# 1-Schematic_dra-30-vox.net
KiCad netlist of a schematic drawn in EasyEDA
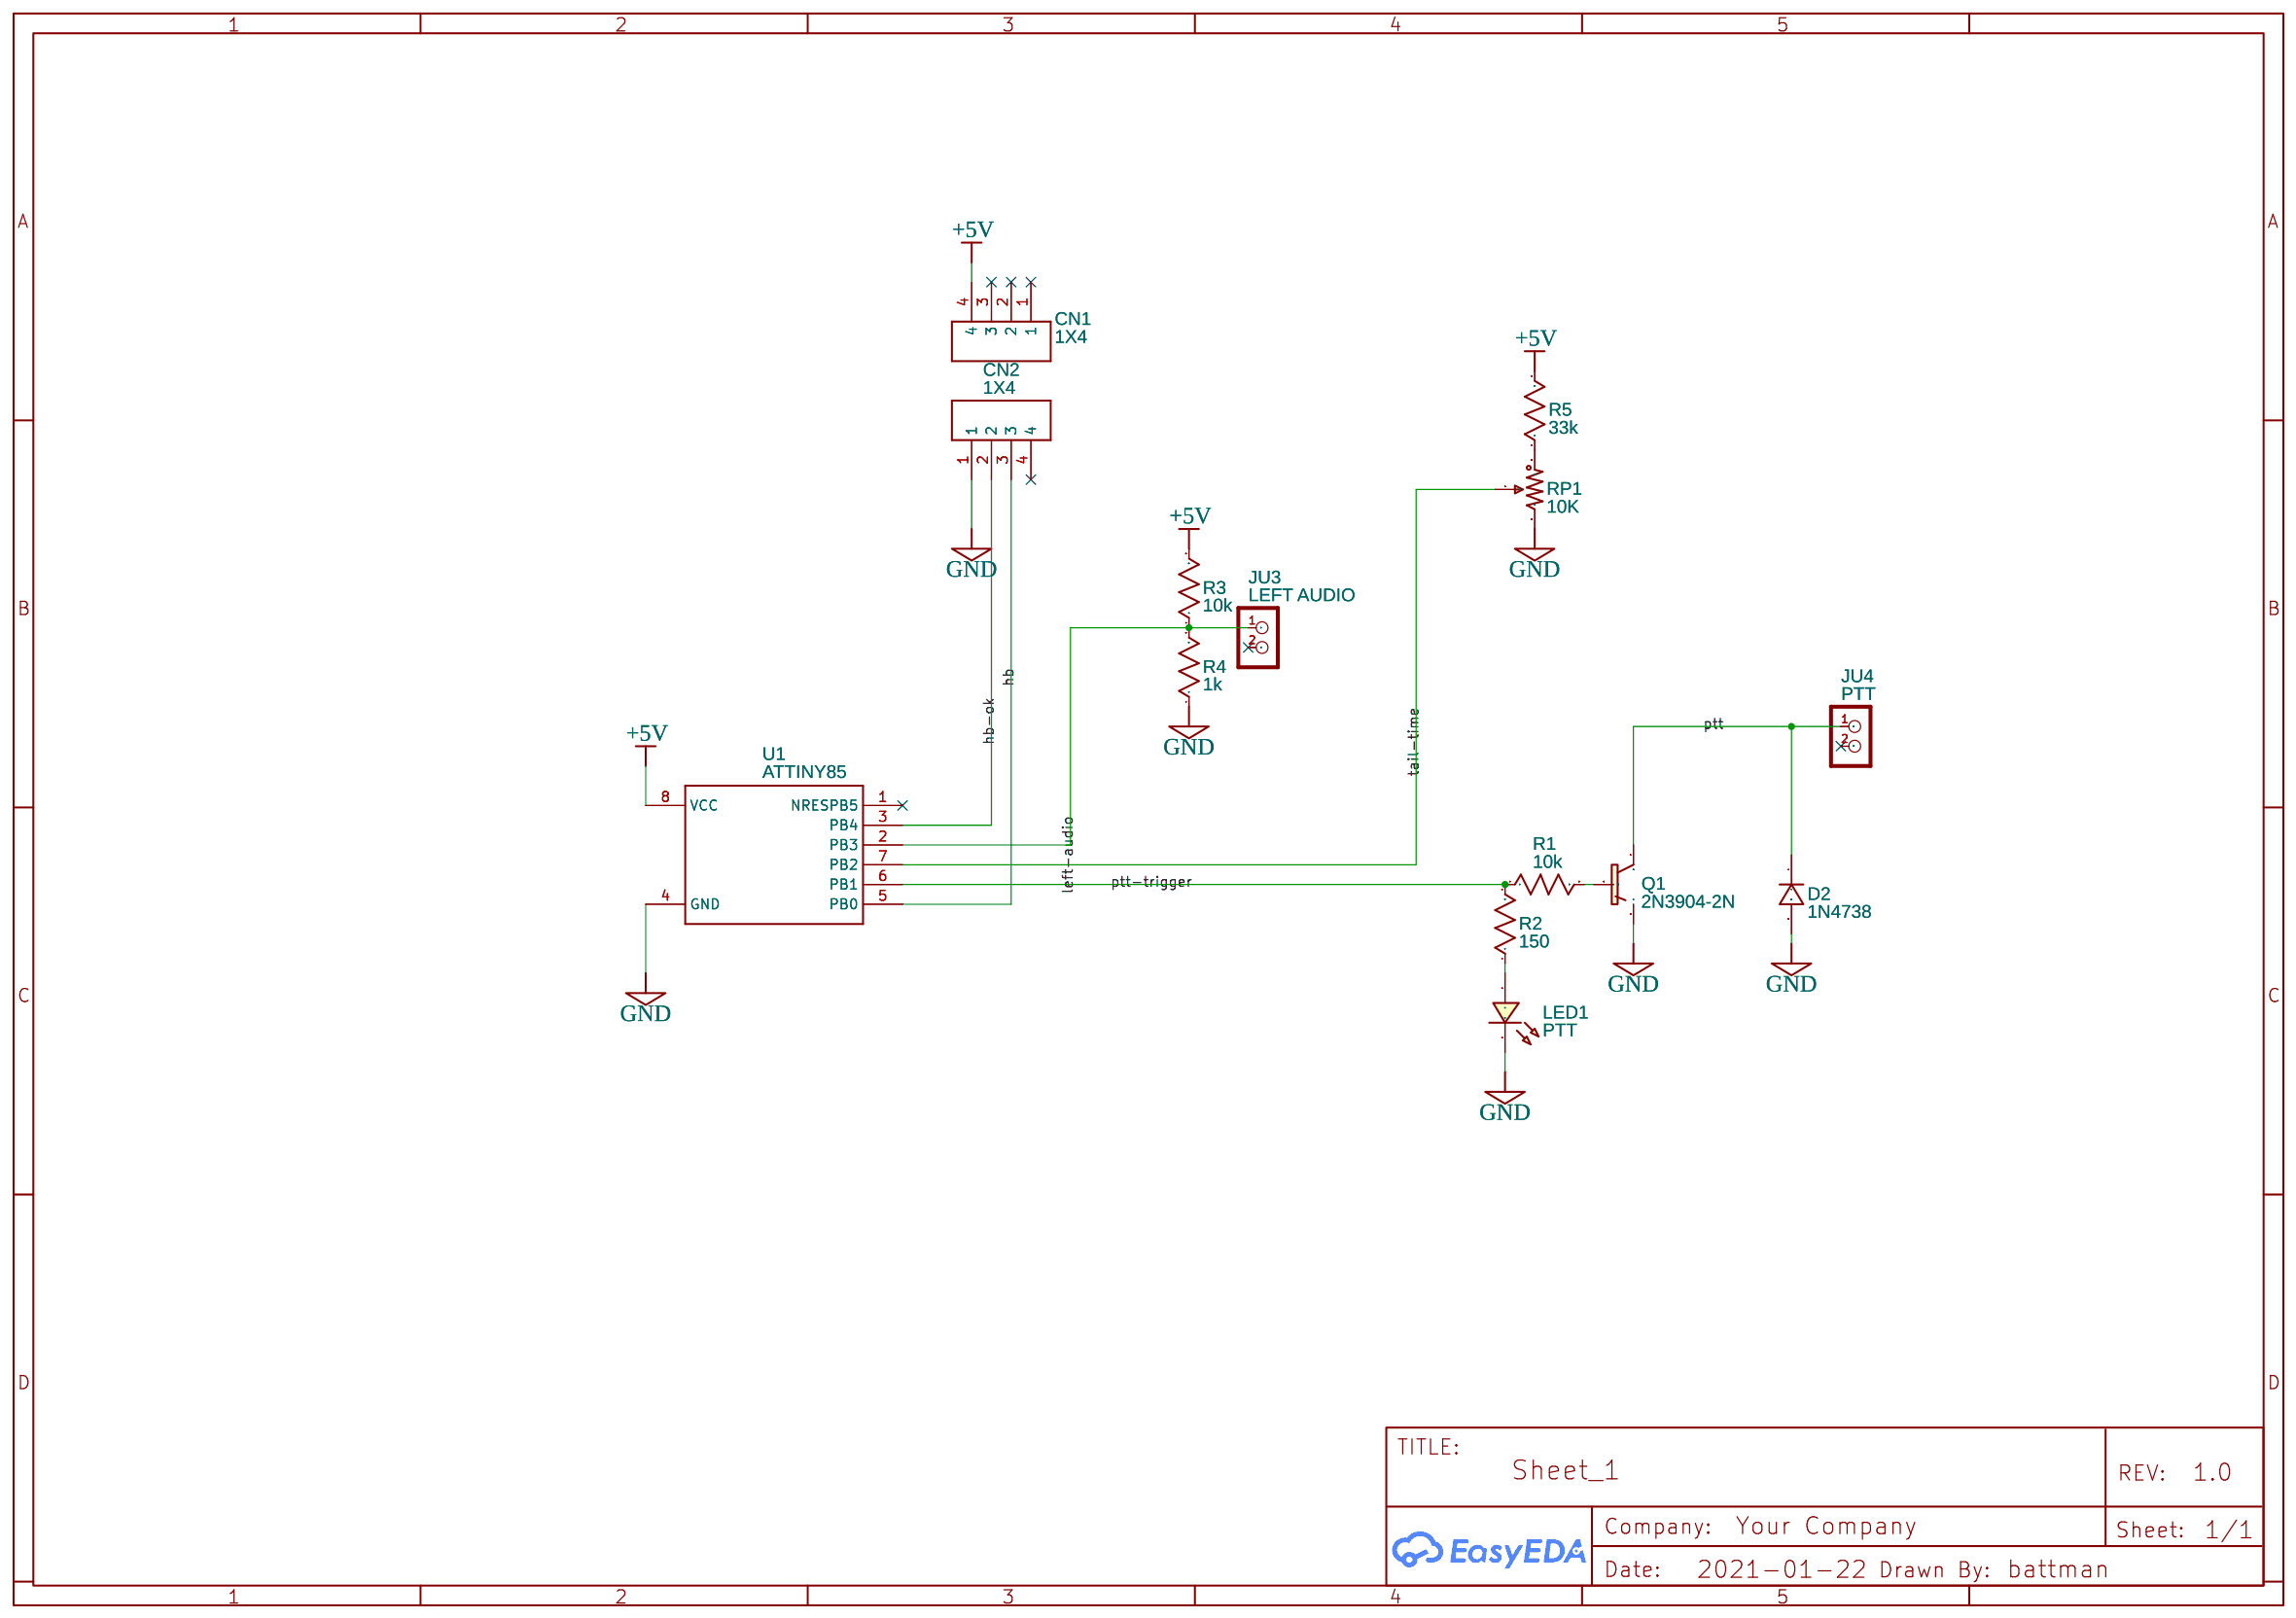
[diagram p0: schematic sheet]

(export (version "E")
  (design (tool "Eeschema 10.0.6"))
  (components
    (comp (ref "CN1") (value "1X4") (libsource (lib "") (part "1X4_1")))
    (comp (ref "CN2") (value "1X4") (libsource (lib "") (part "1X4")))
    (comp (ref "D2")
      (value "1N4738")
      (fields (field (name "BOM_Manufacturer Part") "1N4007") (field (name "BOM_Supplier Part") "C106903"))
      (libsource (lib "") (part "1N4007"))
    )
    (comp (ref "JU3") (value "LEFT AUDIO") (libsource (lib "") (part "CON_HEADER_1X02-PTH")))
    (comp (ref "JU4") (value "PTT") (libsource (lib "") (part "CON_HEADER_1X02-PTH")))
    (comp (ref "LED1")
      (value "PTT")
      (fields
        (field (name "BOM_Manufacturer Part") "333-2SURD/S530-A3")
        (field (name "BOM_Supplier Part") "C87271")
      )
      (libsource (lib "") (part "LED-TH-5mm_R"))
    )
    (comp (ref "Q1") (value "2N3904-2N") (libsource (lib "") (part "2N3904-2N")))
    (comp (ref "R1") (value "10k") (libsource (lib "") (part "R_AXIAL-0.3_US_1")))
    (comp (ref "R2") (value "150") (libsource (lib "") (part "R_AXIAL-0.3_US")))
    (comp (ref "R3") (value "10k") (libsource (lib "") (part "R_AXIAL-0.3_US")))
    (comp (ref "R4") (value "1k") (libsource (lib "") (part "R_AXIAL-0.3_US")))
    (comp (ref "R5") (value "33k") (libsource (lib "") (part "R_AXIAL-0.3_US")))
    (comp (ref "RP1") (value "10K") (libsource (lib "") (part "R_3386P_US")))
    (comp (ref "U1") (value "ATTINY85") (libsource (lib "") (part "ATTINY85V-10P")))
  )
  (nets
    (net (code "1") (name "+5V") (class "Default")
      (node (ref "CN1") (pin "4") (pinfunction "4_4") (pintype "unspecified"))
      (node (ref "R3") (pin "2") (pinfunction "2_2") (pintype "unspecified"))
      (node (ref "R5") (pin "2") (pinfunction "2_2") (pintype "unspecified"))
      (node (ref "U1") (pin "8") (pinfunction "VCC_8") (pintype "passive"))
    )
    (net (code "2") (name "/hb") (class "Default")
      (node (ref "CN2") (pin "3") (pinfunction "3_3") (pintype "unspecified"))
      (node (ref "U1") (pin "5") (pinfunction "PB0_5") (pintype "unspecified"))
    )
    (net (code "3") (name "/hb-ok") (class "Default")
      (node (ref "CN2") (pin "2") (pinfunction "2_2") (pintype "unspecified"))
      (node (ref "U1") (pin "3") (pinfunction "PB4_3") (pintype "unspecified"))
    )
    (net (code "4") (name "/left-audio") (class "Default")
      (node (ref "JU3") (pin "1") (pinfunction "1_1") (pintype "unspecified"))
      (node (ref "R3") (pin "1") (pinfunction "1_1") (pintype "unspecified"))
      (node (ref "R4") (pin "2") (pinfunction "2_2") (pintype "unspecified"))
      (node (ref "U1") (pin "2") (pinfunction "PB3_2") (pintype "unspecified"))
    )
    (net (code "5") (name "/ptt") (class "Default")
      (node (ref "D2") (pin "1") (pinfunction "1_1") (pintype "unspecified"))
      (node (ref "JU4") (pin "1") (pinfunction "1_1") (pintype "unspecified"))
      (node (ref "Q1") (pin "1") (pinfunction "C_1") (pintype "unspecified"))
    )
    (net (code "6") (name "/ptt-trigger") (class "Default")
      (node (ref "R1") (pin "1") (pinfunction "1_1") (pintype "unspecified"))
      (node (ref "R2") (pin "2") (pinfunction "2_2") (pintype "unspecified"))
      (node (ref "U1") (pin "6") (pinfunction "PB1_6") (pintype "unspecified"))
    )
    (net (code "7") (name "/tail-time") (class "Default")
      (node (ref "RP1") (pin "2") (pinfunction "2_2") (pintype "unspecified"))
      (node (ref "U1") (pin "7") (pinfunction "PB2_7") (pintype "unspecified"))
    )
    (net (code "8") (name "GND") (class "Default")
      (node (ref "CN2") (pin "1") (pinfunction "1_1") (pintype "unspecified"))
      (node (ref "D2") (pin "2") (pinfunction "2_2") (pintype "unspecified"))
      (node (ref "LED1") (pin "2") (pinfunction "2_2") (pintype "unspecified"))
      (node (ref "Q1") (pin "3") (pinfunction "E_3") (pintype "unspecified"))
      (node (ref "R4") (pin "1") (pinfunction "1_1") (pintype "unspecified"))
      (node (ref "RP1") (pin "3") (pinfunction "3_3") (pintype "unspecified"))
      (node (ref "U1") (pin "4") (pinfunction "GND_4") (pintype "passive"))
    )
    (net (code "9") (name "Net-(LED1-Pad1)") (class "Default")
      (node (ref "LED1") (pin "1") (pinfunction "1_1") (pintype "unspecified"))
      (node (ref "R2") (pin "1") (pinfunction "1_1") (pintype "unspecified"))
    )
    (net (code "10") (name "Net-(Q1-B)") (class "Default")
      (node (ref "Q1") (pin "2") (pinfunction "B_2") (pintype "unspecified"))
      (node (ref "R1") (pin "2") (pinfunction "2_2") (pintype "unspecified"))
    )
    (net (code "11") (name "Net-(R5-Pad1)") (class "Default")
      (node (ref "R5") (pin "1") (pinfunction "1_1") (pintype "unspecified"))
      (node (ref "RP1") (pin "1") (pinfunction "1_1") (pintype "unspecified"))
    )
    (net (code "12") (name "unconnected-(CN1-Pad1)") (class "Default")
      (node (ref "CN1") (pin "1") (pinfunction "1_1") (pintype "unspecified+no_connect"))
    )
    (net (code "13") (name "unconnected-(CN1-Pad2)") (class "Default")
      (node (ref "CN1") (pin "2") (pinfunction "2_2") (pintype "unspecified+no_connect"))
    )
    (net (code "14") (name "unconnected-(CN1-Pad3)") (class "Default")
      (node (ref "CN1") (pin "3") (pinfunction "3_3") (pintype "unspecified+no_connect"))
    )
    (net (code "15") (name "unconnected-(CN2-Pad4)") (class "Default")
      (node (ref "CN2") (pin "4") (pinfunction "4_4") (pintype "unspecified+no_connect"))
    )
    (net (code "16") (name "unconnected-(JU3-Pad2)") (class "Default")
      (node (ref "JU3") (pin "2") (pinfunction "2_2") (pintype "unspecified+no_connect"))
    )
    (net (code "17") (name "unconnected-(JU4-Pad2)") (class "Default")
      (node (ref "JU4") (pin "2") (pinfunction "2_2") (pintype "unspecified+no_connect"))
    )
    (net (code "18") (name "unconnected-(U1-NRESPB5-Pad1)") (class "Default")
      (node (ref "U1") (pin "1") (pinfunction "NRESPB5_1") (pintype "unspecified+no_connect"))
    )
  )
)
